# 2023-04-01_LN2_Autofill_Connectors_-_Cop.net
KiCad netlist of a schematic drawn in EAGLE
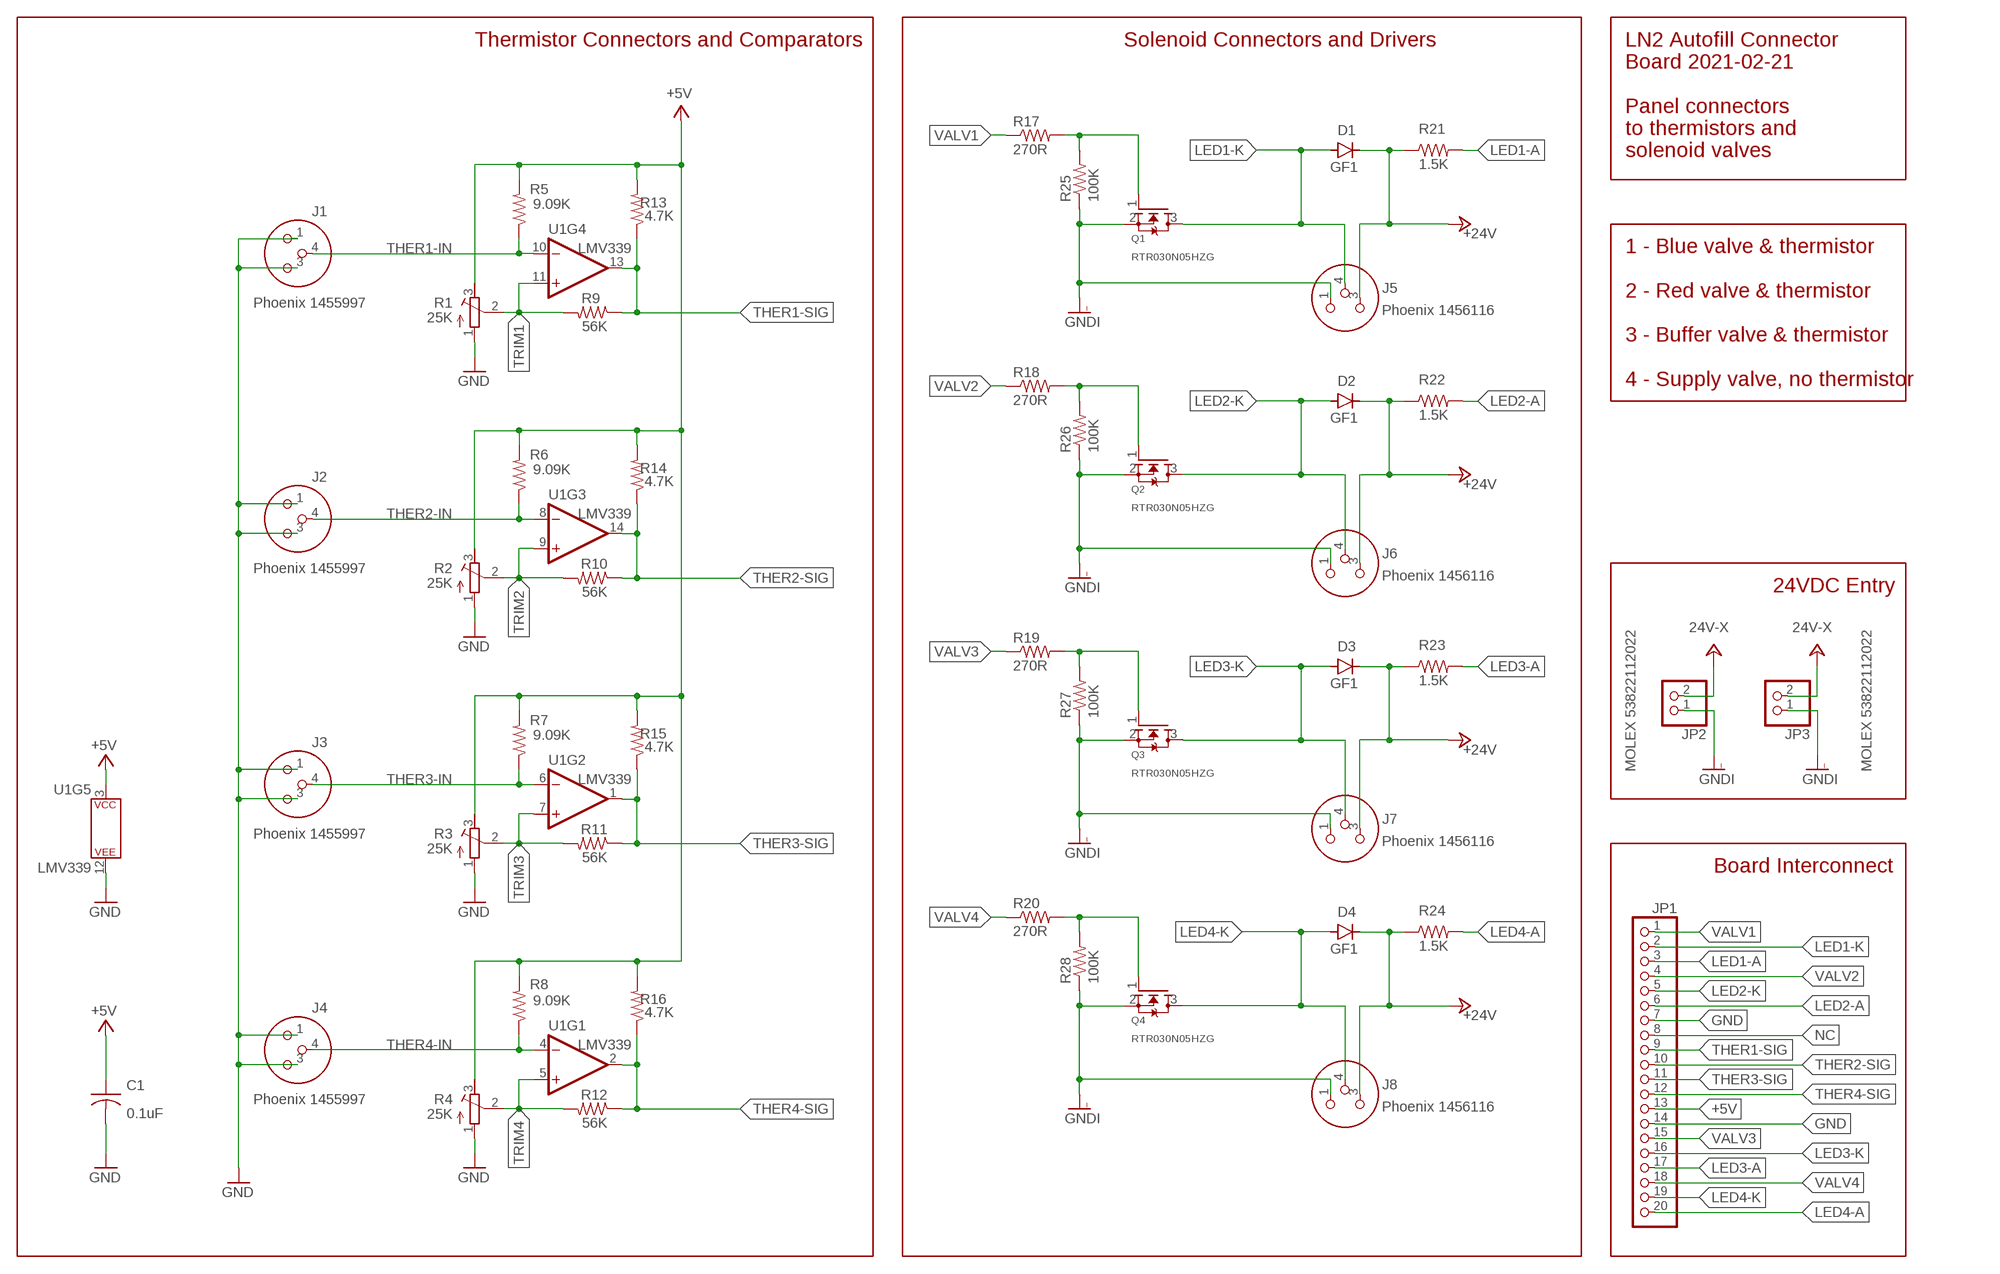
[diagram p0: schematic, sheet 1]

(export (version "E")
  (design (tool "Eeschema 10.0.6"))
  (components
    (comp (ref "C1")
      (value "0.1uF")
      (footprint "eagle-import:C0805")
      (libsource (lib "eagle-import") (part "C-USC0805"))
    )
    (comp (ref "D1")
      (value "GF1")
      (footprint "eagle-import:SMA-DO214AC")
      (libsource (lib "eagle-import") (part "GF1"))
    )
    (comp (ref "D2")
      (value "GF1")
      (footprint "eagle-import:SMA-DO214AC")
      (libsource (lib "eagle-import") (part "GF1"))
    )
    (comp (ref "D3")
      (value "GF1")
      (footprint "eagle-import:SMA-DO214AC")
      (libsource (lib "eagle-import") (part "GF1"))
    )
    (comp (ref "D4")
      (value "GF1")
      (footprint "eagle-import:SMA-DO214AC")
      (libsource (lib "eagle-import") (part "GF1"))
    )
    (comp (ref "J1")
      (value "Phoenix 1455997")
      (footprint "eagle-import:PHOENIX-3PIN")
      (libsource (lib "eagle-import") (part "PHOENIX-3PIN-MALE"))
    )
    (comp (ref "J2")
      (value "Phoenix 1455997")
      (footprint "eagle-import:PHOENIX-3PIN")
      (libsource (lib "eagle-import") (part "PHOENIX-3PIN-MALE"))
    )
    (comp (ref "J3")
      (value "Phoenix 1455997")
      (footprint "eagle-import:PHOENIX-3PIN")
      (libsource (lib "eagle-import") (part "PHOENIX-3PIN-MALE"))
    )
    (comp (ref "J4")
      (value "Phoenix 1455997")
      (footprint "eagle-import:PHOENIX-3PIN")
      (libsource (lib "eagle-import") (part "PHOENIX-3PIN-MALE"))
    )
    (comp (ref "J5")
      (value "Phoenix 1456116")
      (footprint "eagle-import:PHOENIX-3PIN-FEMALE")
      (libsource (lib "eagle-import") (part "PHOENIX-3PIN-FEMALE"))
    )
    (comp (ref "J6")
      (value "Phoenix 1456116")
      (footprint "eagle-import:PHOENIX-3PIN-FEMALE")
      (libsource (lib "eagle-import") (part "PHOENIX-3PIN-FEMALE"))
    )
    (comp (ref "J7")
      (value "Phoenix 1456116")
      (footprint "eagle-import:PHOENIX-3PIN-FEMALE")
      (libsource (lib "eagle-import") (part "PHOENIX-3PIN-FEMALE"))
    )
    (comp (ref "J8")
      (value "Phoenix 1456116")
      (footprint "eagle-import:PHOENIX-3PIN-FEMALE")
      (libsource (lib "eagle-import") (part "PHOENIX-3PIN-FEMALE"))
    )
    (comp (ref "JP1")
      (value "PINHD-1X20")
      (footprint "eagle-import:1X20")
      (libsource (lib "eagle-import") (part "PINHD-1X20"))
    )
    (comp (ref "JP2")
      (value "MOLEX 53822112022")
      (footprint "eagle-import:MOLEX-02-VERT")
      (libsource (lib "eagle-import") (part "PINHD-1X2MOLEX-02-VERT"))
    )
    (comp (ref "JP3")
      (value "MOLEX 53822112022")
      (footprint "eagle-import:MOLEX-02-VERT")
      (libsource (lib "eagle-import") (part "PINHD-1X2MOLEX-02-VERT"))
    )
    (comp (ref "Q1")
      (value "RTR030N05HZG")
      (footprint "eagle-import:SOT23")
      (libsource (lib "eagle-import") (part "MOSFET-NREFLOW"))
    )
    (comp (ref "Q2")
      (value "RTR030N05HZG")
      (footprint "eagle-import:SOT23")
      (libsource (lib "eagle-import") (part "MOSFET-NREFLOW"))
    )
    (comp (ref "Q3")
      (value "RTR030N05HZG")
      (footprint "eagle-import:SOT23")
      (libsource (lib "eagle-import") (part "MOSFET-NREFLOW"))
    )
    (comp (ref "Q4")
      (value "RTR030N05HZG")
      (footprint "eagle-import:SOT23")
      (libsource (lib "eagle-import") (part "MOSFET-NREFLOW"))
    )
    (comp (ref "R1")
      (value "25K")
      (footprint "eagle-import:RTRIM3296Y")
      (libsource (lib "eagle-import") (part "R-TRIMM3296Y"))
    )
    (comp (ref "R2")
      (value "25K")
      (footprint "eagle-import:RTRIM3296Y")
      (libsource (lib "eagle-import") (part "R-TRIMM3296Y"))
    )
    (comp (ref "R3")
      (value "25K")
      (footprint "eagle-import:RTRIM3296Y")
      (libsource (lib "eagle-import") (part "R-TRIMM3296Y"))
    )
    (comp (ref "R4")
      (value "25K")
      (footprint "eagle-import:RTRIM3296Y")
      (libsource (lib "eagle-import") (part "R-TRIMM3296Y"))
    )
    (comp (ref "R5")
      (value "9.09K")
      (footprint "eagle-import:R0805")
      (libsource (lib "eagle-import") (part "R-US_R0805"))
    )
    (comp (ref "R6")
      (value "9.09K")
      (footprint "eagle-import:R0805")
      (libsource (lib "eagle-import") (part "R-US_R0805"))
    )
    (comp (ref "R7")
      (value "9.09K")
      (footprint "eagle-import:R0805")
      (libsource (lib "eagle-import") (part "R-US_R0805"))
    )
    (comp (ref "R8")
      (value "9.09K")
      (footprint "eagle-import:R0805")
      (libsource (lib "eagle-import") (part "R-US_R0805"))
    )
    (comp (ref "R9")
      (value "56K")
      (footprint "eagle-import:R0805")
      (libsource (lib "eagle-import") (part "R-US_R0805"))
    )
    (comp (ref "R10")
      (value "56K")
      (footprint "eagle-import:R0805")
      (libsource (lib "eagle-import") (part "R-US_R0805"))
    )
    (comp (ref "R11")
      (value "56K")
      (footprint "eagle-import:R0805")
      (libsource (lib "eagle-import") (part "R-US_R0805"))
    )
    (comp (ref "R12")
      (value "56K")
      (footprint "eagle-import:R0805")
      (libsource (lib "eagle-import") (part "R-US_R0805"))
    )
    (comp (ref "R13")
      (value "4.7K")
      (footprint "eagle-import:R0805")
      (libsource (lib "eagle-import") (part "R-US_R0805"))
    )
    (comp (ref "R14")
      (value "4.7K")
      (footprint "eagle-import:R0805")
      (libsource (lib "eagle-import") (part "R-US_R0805"))
    )
    (comp (ref "R15")
      (value "4.7K")
      (footprint "eagle-import:R0805")
      (libsource (lib "eagle-import") (part "R-US_R0805"))
    )
    (comp (ref "R16")
      (value "4.7K")
      (footprint "eagle-import:R0805")
      (libsource (lib "eagle-import") (part "R-US_R0805"))
    )
    (comp (ref "R17")
      (value "270R")
      (footprint "eagle-import:R0805")
      (libsource (lib "eagle-import") (part "R-US_R0805"))
    )
    (comp (ref "R18")
      (value "270R")
      (footprint "eagle-import:R0805")
      (libsource (lib "eagle-import") (part "R-US_R0805"))
    )
    (comp (ref "R19")
      (value "270R")
      (footprint "eagle-import:R0805")
      (libsource (lib "eagle-import") (part "R-US_R0805"))
    )
    (comp (ref "R20")
      (value "270R")
      (footprint "eagle-import:R0805")
      (libsource (lib "eagle-import") (part "R-US_R0805"))
    )
    (comp (ref "R21")
      (value "1.5K")
      (footprint "eagle-import:R0805")
      (libsource (lib "eagle-import") (part "R-US_R0805"))
    )
    (comp (ref "R22")
      (value "1.5K")
      (footprint "eagle-import:R0805")
      (libsource (lib "eagle-import") (part "R-US_R0805"))
    )
    (comp (ref "R23")
      (value "1.5K")
      (footprint "eagle-import:R0805")
      (libsource (lib "eagle-import") (part "R-US_R0805"))
    )
    (comp (ref "R24")
      (value "1.5K")
      (footprint "eagle-import:R0805")
      (libsource (lib "eagle-import") (part "R-US_R0805"))
    )
    (comp (ref "R25")
      (value "100K")
      (footprint "eagle-import:R0805")
      (libsource (lib "eagle-import") (part "R-US_R0805"))
    )
    (comp (ref "R26")
      (value "100K")
      (footprint "eagle-import:R0805")
      (libsource (lib "eagle-import") (part "R-US_R0805"))
    )
    (comp (ref "R27")
      (value "100K")
      (footprint "eagle-import:R0805")
      (libsource (lib "eagle-import") (part "R-US_R0805"))
    )
    (comp (ref "R28")
      (value "100K")
      (footprint "eagle-import:R0805")
      (libsource (lib "eagle-import") (part "R-US_R0805"))
    )
    (comp (ref "U1")
      (value "LMV339")
      (footprint "eagle-import:SOIC127P599X175-14")
      (libsource (lib "eagle-import") (part "LM339SOIC-14"))
    )
  )
  (nets
    (net (code "1") (name "+5V") (class "Default")
      (node (ref "C1") (pin "1") (pinfunction "1_1") (pintype "passive"))
      (node (ref "JP1") (pin "13") (pinfunction "13_13") (pintype "passive"))
      (node (ref "R1") (pin "3") (pinfunction "E_3") (pintype "passive"))
      (node (ref "R13") (pin "2") (pinfunction "2_2") (pintype "passive"))
      (node (ref "R14") (pin "2") (pinfunction "2_2") (pintype "passive"))
      (node (ref "R15") (pin "2") (pinfunction "2_2") (pintype "passive"))
      (node (ref "R16") (pin "2") (pinfunction "2_2") (pintype "passive"))
      (node (ref "R2") (pin "3") (pinfunction "E_3") (pintype "passive"))
      (node (ref "R3") (pin "3") (pinfunction "E_3") (pintype "passive"))
      (node (ref "R4") (pin "3") (pinfunction "E_3") (pintype "passive"))
      (node (ref "R5") (pin "2") (pinfunction "2_2") (pintype "passive"))
      (node (ref "R6") (pin "2") (pinfunction "2_2") (pintype "passive"))
      (node (ref "R7") (pin "2") (pinfunction "2_2") (pintype "passive"))
      (node (ref "R8") (pin "2") (pinfunction "2_2") (pintype "passive"))
      (node (ref "U1") (pin "3") (pinfunction "P$V+_3") (pintype "bidirectional"))
    )
    (net (code "2") (name "+24V") (class "Default")
      (node (ref "D1") (pin "K") (pinfunction "C_K") (pintype "passive"))
      (node (ref "D2") (pin "K") (pinfunction "C_K") (pintype "passive"))
      (node (ref "D3") (pin "K") (pinfunction "C_K") (pintype "passive"))
      (node (ref "D4") (pin "K") (pinfunction "C_K") (pintype "passive"))
      (node (ref "J5") (pin "3") (pinfunction "3_3") (pintype "passive"))
      (node (ref "J6") (pin "3") (pinfunction "3_3") (pintype "passive"))
      (node (ref "J7") (pin "3") (pinfunction "3_3") (pintype "passive"))
      (node (ref "J8") (pin "3") (pinfunction "3_3") (pintype "passive"))
      (node (ref "JP2") (pin "2") (pinfunction "2_2") (pintype "passive"))
      (node (ref "JP3") (pin "2") (pinfunction "2_2") (pintype "passive"))
      (node (ref "R21") (pin "1") (pinfunction "1_1") (pintype "passive"))
      (node (ref "R22") (pin "1") (pinfunction "1_1") (pintype "passive"))
      (node (ref "R23") (pin "1") (pinfunction "1_1") (pintype "passive"))
      (node (ref "R24") (pin "1") (pinfunction "1_1") (pintype "passive"))
    )
    (net (code "3") (name "/THER1-IN") (class "Default")
      (node (ref "J1") (pin "4") (pinfunction "4_4") (pintype "passive"))
      (node (ref "R5") (pin "1") (pinfunction "1_1") (pintype "passive"))
      (node (ref "U1") (pin "10") (pinfunction "-IN_10") (pintype "input"))
    )
    (net (code "4") (name "/THER2-IN") (class "Default")
      (node (ref "J2") (pin "4") (pinfunction "4_4") (pintype "passive"))
      (node (ref "R6") (pin "1") (pinfunction "1_1") (pintype "passive"))
      (node (ref "U1") (pin "8") (pinfunction "-IN_8") (pintype "input"))
    )
    (net (code "5") (name "/THER3-IN") (class "Default")
      (node (ref "J3") (pin "4") (pinfunction "4_4") (pintype "passive"))
      (node (ref "R7") (pin "1") (pinfunction "1_1") (pintype "passive"))
      (node (ref "U1") (pin "6") (pinfunction "-IN_6") (pintype "input"))
    )
    (net (code "6") (name "/THER4-IN") (class "Default")
      (node (ref "J4") (pin "4") (pinfunction "4_4") (pintype "passive"))
      (node (ref "R8") (pin "1") (pinfunction "1_1") (pintype "passive"))
      (node (ref "U1") (pin "4") (pinfunction "-IN_4") (pintype "input"))
    )
    (net (code "7") (name "GND") (class "Default")
      (node (ref "C1") (pin "2") (pinfunction "2_2") (pintype "passive"))
      (node (ref "J1") (pin "1") (pinfunction "1_1") (pintype "passive"))
      (node (ref "J1") (pin "3") (pinfunction "3_3") (pintype "passive"))
      (node (ref "J2") (pin "1") (pinfunction "1_1") (pintype "passive"))
      (node (ref "J2") (pin "3") (pinfunction "3_3") (pintype "passive"))
      (node (ref "J3") (pin "1") (pinfunction "1_1") (pintype "passive"))
      (node (ref "J3") (pin "3") (pinfunction "3_3") (pintype "passive"))
      (node (ref "J4") (pin "1") (pinfunction "1_1") (pintype "passive"))
      (node (ref "J4") (pin "3") (pinfunction "3_3") (pintype "passive"))
      (node (ref "JP1") (pin "14") (pinfunction "14_14") (pintype "passive"))
      (node (ref "JP1") (pin "7") (pinfunction "7_7") (pintype "passive"))
      (node (ref "R1") (pin "1") (pinfunction "A_1") (pintype "passive"))
      (node (ref "R2") (pin "1") (pinfunction "A_1") (pintype "passive"))
      (node (ref "R3") (pin "1") (pinfunction "A_1") (pintype "passive"))
      (node (ref "R4") (pin "1") (pinfunction "A_1") (pintype "passive"))
      (node (ref "U1") (pin "12") (pinfunction "P$V-_12") (pintype "bidirectional"))
    )
    (net (code "8") (name "GNDI") (class "Default")
      (node (ref "J5") (pin "1") (pinfunction "1_1") (pintype "passive"))
      (node (ref "J6") (pin "1") (pinfunction "1_1") (pintype "passive"))
      (node (ref "J7") (pin "1") (pinfunction "1_1") (pintype "passive"))
      (node (ref "J8") (pin "1") (pinfunction "1_1") (pintype "passive"))
      (node (ref "JP2") (pin "1") (pinfunction "1_1") (pintype "passive"))
      (node (ref "JP3") (pin "1") (pinfunction "1_1") (pintype "passive"))
      (node (ref "Q1") (pin "2") (pinfunction "S_2") (pintype "bidirectional"))
      (node (ref "Q2") (pin "2") (pinfunction "S_2") (pintype "bidirectional"))
      (node (ref "Q3") (pin "2") (pinfunction "S_2") (pintype "bidirectional"))
      (node (ref "Q4") (pin "2") (pinfunction "S_2") (pintype "bidirectional"))
      (node (ref "R25") (pin "1") (pinfunction "1_1") (pintype "passive"))
      (node (ref "R26") (pin "1") (pinfunction "1_1") (pintype "passive"))
      (node (ref "R27") (pin "1") (pinfunction "1_1") (pintype "passive"))
      (node (ref "R28") (pin "1") (pinfunction "1_1") (pintype "passive"))
    )
    (net (code "9") (name "LED1-A") (class "Default")
      (node (ref "JP1") (pin "3") (pinfunction "3_3") (pintype "passive"))
      (node (ref "R21") (pin "2") (pinfunction "2_2") (pintype "passive"))
    )
    (net (code "10") (name "LED1-K") (class "Default")
      (node (ref "D1") (pin "A") (pinfunction "A_A") (pintype "passive"))
      (node (ref "J5") (pin "4") (pinfunction "4_4") (pintype "passive"))
      (node (ref "JP1") (pin "2") (pinfunction "2_2") (pintype "passive"))
      (node (ref "Q1") (pin "3") (pinfunction "D_3") (pintype "bidirectional"))
    )
    (net (code "11") (name "LED2-A") (class "Default")
      (node (ref "JP1") (pin "6") (pinfunction "6_6") (pintype "passive"))
      (node (ref "R22") (pin "2") (pinfunction "2_2") (pintype "passive"))
    )
    (net (code "12") (name "LED2-K") (class "Default")
      (node (ref "D2") (pin "A") (pinfunction "A_A") (pintype "passive"))
      (node (ref "J6") (pin "4") (pinfunction "4_4") (pintype "passive"))
      (node (ref "JP1") (pin "5") (pinfunction "5_5") (pintype "passive"))
      (node (ref "Q2") (pin "3") (pinfunction "D_3") (pintype "bidirectional"))
    )
    (net (code "13") (name "LED3-A") (class "Default")
      (node (ref "JP1") (pin "17") (pinfunction "17_17") (pintype "passive"))
      (node (ref "R23") (pin "2") (pinfunction "2_2") (pintype "passive"))
    )
    (net (code "14") (name "LED3-K") (class "Default")
      (node (ref "D3") (pin "A") (pinfunction "A_A") (pintype "passive"))
      (node (ref "J7") (pin "4") (pinfunction "4_4") (pintype "passive"))
      (node (ref "JP1") (pin "16") (pinfunction "16_16") (pintype "passive"))
      (node (ref "Q3") (pin "3") (pinfunction "D_3") (pintype "bidirectional"))
    )
    (net (code "15") (name "LED4-A") (class "Default")
      (node (ref "JP1") (pin "20") (pinfunction "20_20") (pintype "passive"))
      (node (ref "R24") (pin "2") (pinfunction "2_2") (pintype "passive"))
    )
    (net (code "16") (name "LED4-K") (class "Default")
      (node (ref "D4") (pin "A") (pinfunction "A_A") (pintype "passive"))
      (node (ref "J8") (pin "4") (pinfunction "4_4") (pintype "passive"))
      (node (ref "JP1") (pin "19") (pinfunction "19_19") (pintype "passive"))
      (node (ref "Q4") (pin "3") (pinfunction "D_3") (pintype "bidirectional"))
    )
    (net (code "17") (name "NC") (class "Default")
      (node (ref "JP1") (pin "8") (pinfunction "8_8") (pintype "passive"))
    )
    (net (code "18") (name "Net-(Q1-G)") (class "Default")
      (node (ref "Q1") (pin "1") (pinfunction "G_1") (pintype "bidirectional"))
      (node (ref "R17") (pin "2") (pinfunction "2_2") (pintype "passive"))
      (node (ref "R25") (pin "2") (pinfunction "2_2") (pintype "passive"))
    )
    (net (code "19") (name "Net-(Q2-G)") (class "Default")
      (node (ref "Q2") (pin "1") (pinfunction "G_1") (pintype "bidirectional"))
      (node (ref "R18") (pin "2") (pinfunction "2_2") (pintype "passive"))
      (node (ref "R26") (pin "2") (pinfunction "2_2") (pintype "passive"))
    )
    (net (code "20") (name "Net-(Q3-G)") (class "Default")
      (node (ref "Q3") (pin "1") (pinfunction "G_1") (pintype "bidirectional"))
      (node (ref "R19") (pin "2") (pinfunction "2_2") (pintype "passive"))
      (node (ref "R27") (pin "2") (pinfunction "2_2") (pintype "passive"))
    )
    (net (code "21") (name "Net-(Q4-G)") (class "Default")
      (node (ref "Q4") (pin "1") (pinfunction "G_1") (pintype "bidirectional"))
      (node (ref "R20") (pin "2") (pinfunction "2_2") (pintype "passive"))
      (node (ref "R28") (pin "2") (pinfunction "2_2") (pintype "passive"))
    )
    (net (code "22") (name "THER1-SIG") (class "Default")
      (node (ref "JP1") (pin "9") (pinfunction "9_9") (pintype "passive"))
      (node (ref "R13") (pin "1") (pinfunction "1_1") (pintype "passive"))
      (node (ref "R9") (pin "1") (pinfunction "1_1") (pintype "passive"))
      (node (ref "U1") (pin "13") (pinfunction "OUT_13") (pintype "output"))
    )
    (net (code "23") (name "THER2-SIG") (class "Default")
      (node (ref "JP1") (pin "10") (pinfunction "10_10") (pintype "passive"))
      (node (ref "R10") (pin "1") (pinfunction "1_1") (pintype "passive"))
      (node (ref "R14") (pin "1") (pinfunction "1_1") (pintype "passive"))
      (node (ref "U1") (pin "14") (pinfunction "OUT_14") (pintype "output"))
    )
    (net (code "24") (name "THER3-SIG") (class "Default")
      (node (ref "JP1") (pin "11") (pinfunction "11_11") (pintype "passive"))
      (node (ref "R11") (pin "1") (pinfunction "1_1") (pintype "passive"))
      (node (ref "R15") (pin "1") (pinfunction "1_1") (pintype "passive"))
      (node (ref "U1") (pin "1") (pinfunction "OUT_1") (pintype "output"))
    )
    (net (code "25") (name "THER4-SIG") (class "Default")
      (node (ref "JP1") (pin "12") (pinfunction "12_12") (pintype "passive"))
      (node (ref "R12") (pin "1") (pinfunction "1_1") (pintype "passive"))
      (node (ref "R16") (pin "1") (pinfunction "1_1") (pintype "passive"))
      (node (ref "U1") (pin "2") (pinfunction "OUT_2") (pintype "output"))
    )
    (net (code "26") (name "TRIM1") (class "Default")
      (node (ref "R1") (pin "2") (pinfunction "S_2") (pintype "passive"))
      (node (ref "R9") (pin "2") (pinfunction "2_2") (pintype "passive"))
      (node (ref "U1") (pin "11") (pinfunction "+IN_11") (pintype "input"))
    )
    (net (code "27") (name "TRIM2") (class "Default")
      (node (ref "R10") (pin "2") (pinfunction "2_2") (pintype "passive"))
      (node (ref "R2") (pin "2") (pinfunction "S_2") (pintype "passive"))
      (node (ref "U1") (pin "9") (pinfunction "+IN_9") (pintype "input"))
    )
    (net (code "28") (name "TRIM3") (class "Default")
      (node (ref "R11") (pin "2") (pinfunction "2_2") (pintype "passive"))
      (node (ref "R3") (pin "2") (pinfunction "S_2") (pintype "passive"))
      (node (ref "U1") (pin "7") (pinfunction "+IN_7") (pintype "input"))
    )
    (net (code "29") (name "TRIM4") (class "Default")
      (node (ref "R12") (pin "2") (pinfunction "2_2") (pintype "passive"))
      (node (ref "R4") (pin "2") (pinfunction "S_2") (pintype "passive"))
      (node (ref "U1") (pin "5") (pinfunction "+IN_5") (pintype "input"))
    )
    (net (code "30") (name "VALV1") (class "Default")
      (node (ref "JP1") (pin "1") (pinfunction "1_1") (pintype "passive"))
      (node (ref "R17") (pin "1") (pinfunction "1_1") (pintype "passive"))
    )
    (net (code "31") (name "VALV2") (class "Default")
      (node (ref "JP1") (pin "4") (pinfunction "4_4") (pintype "passive"))
      (node (ref "R18") (pin "1") (pinfunction "1_1") (pintype "passive"))
    )
    (net (code "32") (name "VALV3") (class "Default")
      (node (ref "JP1") (pin "15") (pinfunction "15_15") (pintype "passive"))
      (node (ref "R19") (pin "1") (pinfunction "1_1") (pintype "passive"))
    )
    (net (code "33") (name "VALV4") (class "Default")
      (node (ref "JP1") (pin "18") (pinfunction "18_18") (pintype "passive"))
      (node (ref "R20") (pin "1") (pinfunction "1_1") (pintype "passive"))
    )
  )
)
